# hdmi_wing.net
KiCad netlist of a schematic drawn in Altium Designer
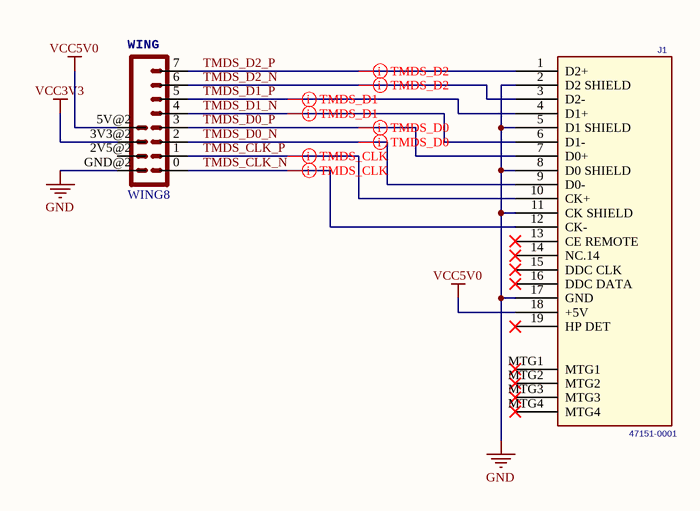
[diagram p0: hdmi_wing.SchDoc]

(export (version "E")
  (design (tool "Eeschema 10.0.6"))
  (components
    (comp (ref "J1")
      (value "47151-0001")
      (footprint "HDMI_S_RA_SMD")
      (description "CONN RCPT 19POS HDMI RT ANG SMD")
      (fields (field (name "MANUFACTURER") "Molex Connector Corporation"))
      (libsource (lib "MH - Connectors") (part "47151-0001"))
    )
    (comp (ref "WING") (value "WING8") (footprint "WINGSIDE_8BIT") (libsource (lib "Papilio") (part "WING8")))
  )
  (nets
    (net (code "1") (name "/TMDS_CLK_N") (class "Default")
      (node (ref "J1") (pin "12") (pinfunction "CK-_12") (pintype "passive"))
      (node (ref "WING") (pin "0") (pinfunction "1_0") (pintype "passive"))
    )
    (net (code "2") (name "/TMDS_CLK_P") (class "Default")
      (node (ref "J1") (pin "10") (pinfunction "CK+_10") (pintype "passive"))
      (node (ref "WING") (pin "1") (pinfunction "2_1") (pintype "passive"))
    )
    (net (code "3") (name "/TMDS_D0_N") (class "Default")
      (node (ref "J1") (pin "9") (pinfunction "D0-_9") (pintype "passive"))
      (node (ref "WING") (pin "2") (pinfunction "3_2") (pintype "passive"))
    )
    (net (code "4") (name "/TMDS_D0_P") (class "Default")
      (node (ref "J1") (pin "7") (pinfunction "D0+_7") (pintype "passive"))
      (node (ref "WING") (pin "3") (pinfunction "4_3") (pintype "passive"))
    )
    (net (code "5") (name "/TMDS_D1_N") (class "Default")
      (node (ref "J1") (pin "6") (pinfunction "D1-_6") (pintype "passive"))
      (node (ref "WING") (pin "4") (pinfunction "5_4") (pintype "passive"))
    )
    (net (code "6") (name "/TMDS_D1_P") (class "Default")
      (node (ref "J1") (pin "4") (pinfunction "D1+_4") (pintype "passive"))
      (node (ref "WING") (pin "5") (pinfunction "6_5") (pintype "passive"))
    )
    (net (code "7") (name "/TMDS_D2_N") (class "Default")
      (node (ref "J1") (pin "3") (pinfunction "D2-_3") (pintype "passive"))
      (node (ref "WING") (pin "6") (pinfunction "7_6") (pintype "passive"))
    )
    (net (code "8") (name "/TMDS_D2_P") (class "Default")
      (node (ref "J1") (pin "1") (pinfunction "D2+_1") (pintype "passive"))
      (node (ref "WING") (pin "7") (pinfunction "8_7") (pintype "passive"))
    )
    (net (code "9") (name "GND") (class "Default")
      (node (ref "J1") (pin "11") (pinfunction "CK_SHIELD_11") (pintype "passive"))
      (node (ref "J1") (pin "17") (pinfunction "GND_17") (pintype "passive"))
      (node (ref "J1") (pin "2") (pinfunction "D2_SHIELD_2") (pintype "passive"))
      (node (ref "J1") (pin "5") (pinfunction "D1_SHIELD_5") (pintype "passive"))
      (node (ref "J1") (pin "8") (pinfunction "D0_SHIELD_8") (pintype "passive"))
      (node (ref "WING") (pin "GND@2") (pinfunction "GND_GND@2") (pintype "passive"))
    )
    (net (code "10") (name "VCC3V3") (class "Default")
      (node (ref "WING") (pin "3V3@2") (pinfunction "3V3_3V3@2") (pintype "passive"))
    )
    (net (code "11") (name "VCC5V0") (class "Default")
      (node (ref "J1") (pin "18") (pinfunction "+5V_18") (pintype "passive"))
      (node (ref "WING") (pin "5V@2") (pinfunction "5V_5V@2") (pintype "passive"))
    )
    (net (code "12") (name "unconnected-(J1-CE_REMOTE-Pad13)") (class "Default")
      (node (ref "J1") (pin "13") (pinfunction "CE_REMOTE_13") (pintype "passive+no_connect"))
    )
    (net (code "13") (name "unconnected-(J1-DDC_CLK-Pad15)") (class "Default")
      (node (ref "J1") (pin "15") (pinfunction "DDC_CLK_15") (pintype "passive+no_connect"))
    )
    (net (code "14") (name "unconnected-(J1-DDC_DATA-Pad16)") (class "Default")
      (node (ref "J1") (pin "16") (pinfunction "DDC_DATA_16") (pintype "passive+no_connect"))
    )
    (net (code "15") (name "unconnected-(J1-HP_DET-Pad19)") (class "Default")
      (node (ref "J1") (pin "19") (pinfunction "HP_DET_19") (pintype "passive+no_connect"))
    )
    (net (code "16") (name "unconnected-(J1-NC.14-Pad14)") (class "Default")
      (node (ref "J1") (pin "14") (pinfunction "NC.14_14") (pintype "passive+no_connect"))
    )
    (net (code "17") (name "unconnected-(J1-PadMTG1)") (class "Default")
      (node (ref "J1") (pin "MTG1") (pinfunction "MTG1_MTG1") (pintype "passive+no_connect"))
    )
    (net (code "18") (name "unconnected-(J1-PadMTG2)") (class "Default")
      (node (ref "J1") (pin "MTG2") (pinfunction "MTG2_MTG2") (pintype "passive+no_connect"))
    )
    (net (code "19") (name "unconnected-(J1-PadMTG3)") (class "Default")
      (node (ref "J1") (pin "MTG3") (pinfunction "MTG3_MTG3") (pintype "passive+no_connect"))
    )
    (net (code "20") (name "unconnected-(J1-PadMTG4)") (class "Default")
      (node (ref "J1") (pin "MTG4") (pinfunction "MTG4_MTG4") (pintype "passive+no_connect"))
    )
    (net (code "21") (name "unconnected-(WING-2V5-Pad2V5@2)") (class "Default")
      (node (ref "WING") (pin "2V5@2") (pinfunction "2V5_2V5@2") (pintype "passive"))
    )
  )
)
